# VS1003.net
KiCad netlist of a schematic drawn in Altium Designer
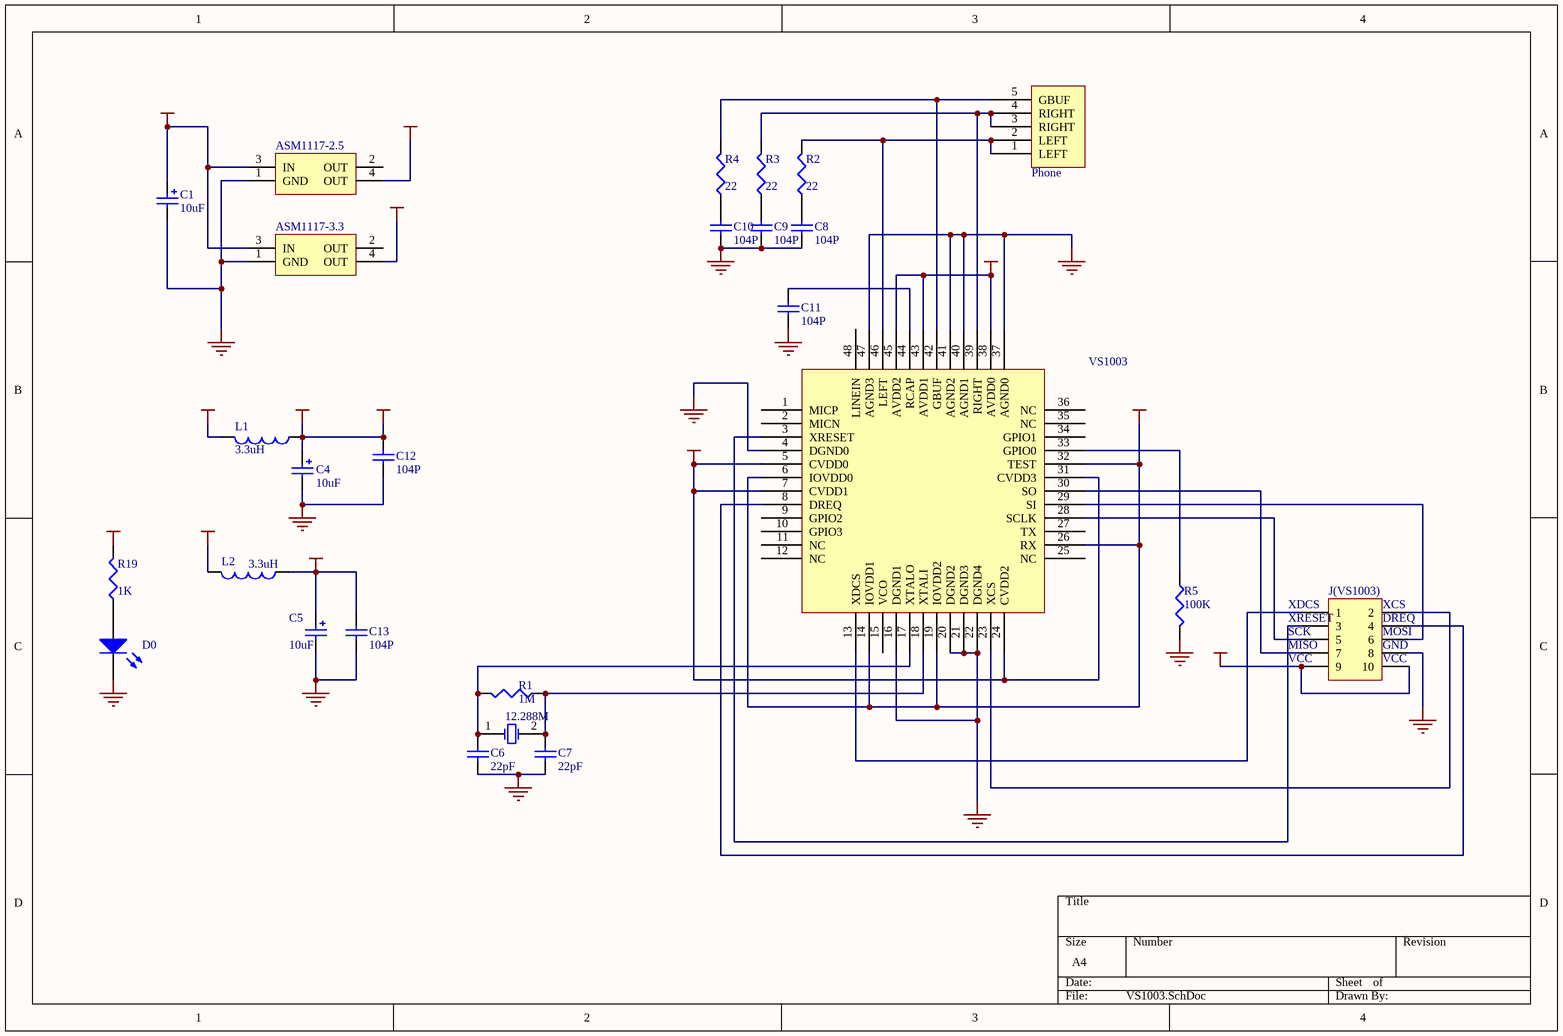
[diagram p0: VS1003.SchDoc]

(export (version "E")
  (design (tool "Eeschema 10.0.6"))
  (components
    (comp (ref "12.288M")
      (value "XTAL")
      (footprint "RAD-0.2")
      (description "Crystal Oscillator")
      (fields (field (name "PUBLISHER") "Altium Limited"))
      (libsource (lib "Miscellaneous Devices") (part "XTAL"))
    )
    (comp (ref "ASM1117-2.5")
      (value "REG1117-5")
      (footprint "ZZ311")
      (description "800mA and 1A Low Dropout Positive Regulator 2.85V, 3.3V, 5V, and Adjustable")
      (fields (field (name "PUBLISHER") "Altium Limited"))
      (libsource (lib "BB Power Mgt Voltage Regulator") (part "REG1117-5"))
    )
    (comp (ref "ASM1117-3.3")
      (value "REG1117-5")
      (footprint "ZZ311")
      (description "800mA and 1A Low Dropout Positive Regulator 2.85V, 3.3V, 5V, and Adjustable")
      (fields (field (name "PUBLISHER") "Altium Limited"))
      (libsource (lib "BB Power Mgt Voltage Regulator") (part "REG1117-5"))
    )
    (comp (ref "C1")
      (value "10uF")
      (footprint "CR3225-1210")
      (description "Polarized Capacitor (Surface Mount)")
      (fields (field (name "Comment") "Cap Pol3") (field (name "PUBLISHER") "Altium Limited"))
      (libsource (lib "Miscellaneous Devices") (part "Cap Pol3"))
    )
    (comp (ref "C4")
      (value "10uF")
      (footprint "CR3225-1210")
      (description "Polarized Capacitor (Surface Mount)")
      (fields (field (name "Comment") "Cap Pol3") (field (name "PUBLISHER") "Altium Limited"))
      (libsource (lib "Miscellaneous Devices") (part "Cap Pol3"))
    )
    (comp (ref "C5")
      (value "10uF")
      (footprint "CR3225-1210")
      (description "Polarized Capacitor (Surface Mount)")
      (fields (field (name "Comment") "Cap Pol3") (field (name "PUBLISHER") "Altium Limited"))
      (libsource (lib "Miscellaneous Devices") (part "Cap Pol3"))
    )
    (comp (ref "C6")
      (value "22pF")
      (footprint "CR2012-0805")
      (description "Capacitor (Semiconductor SIM Model)")
      (fields (field (name "Comment") "Cap Semi") (field (name "PUBLISHER") "Altium Limited"))
      (libsource (lib "Miscellaneous Devices") (part "Cap Semi"))
    )
    (comp (ref "C7")
      (value "22pF")
      (footprint "CR2012-0805")
      (description "Capacitor (Semiconductor SIM Model)")
      (fields (field (name "Comment") "Cap Semi") (field (name "PUBLISHER") "Altium Limited"))
      (libsource (lib "Miscellaneous Devices") (part "Cap Semi"))
    )
    (comp (ref "C8")
      (value "104P")
      (footprint "CR2012-0805")
      (description "Capacitor (Semiconductor SIM Model)")
      (fields (field (name "Comment") "Cap Semi") (field (name "PUBLISHER") "Altium Limited"))
      (libsource (lib "Miscellaneous Devices") (part "Cap Semi"))
    )
    (comp (ref "C9")
      (value "104P")
      (footprint "CR2012-0805")
      (description "Capacitor (Semiconductor SIM Model)")
      (fields (field (name "Comment") "Cap Semi") (field (name "PUBLISHER") "Altium Limited"))
      (libsource (lib "Miscellaneous Devices") (part "Cap Semi"))
    )
    (comp (ref "C10")
      (value "104P")
      (footprint "CR2012-0805")
      (description "Capacitor (Semiconductor SIM Model)")
      (fields (field (name "Comment") "Cap Semi") (field (name "PUBLISHER") "Altium Limited"))
      (libsource (lib "Miscellaneous Devices") (part "Cap Semi"))
    )
    (comp (ref "C11")
      (value "104P")
      (footprint "CR2012-0805")
      (description "Capacitor (Semiconductor SIM Model)")
      (fields (field (name "Comment") "Cap Semi") (field (name "PUBLISHER") "Altium Limited"))
      (libsource (lib "Miscellaneous Devices") (part "Cap Semi"))
    )
    (comp (ref "C12")
      (value "104P")
      (footprint "CR2012-0805")
      (description "Capacitor (Semiconductor SIM Model)")
      (fields (field (name "Comment") "Cap Semi") (field (name "PUBLISHER") "Altium Limited"))
      (libsource (lib "Miscellaneous Devices") (part "Cap Semi"))
    )
    (comp (ref "C13")
      (value "104P")
      (footprint "CR2012-0805")
      (description "Capacitor (Semiconductor SIM Model)")
      (fields (field (name "Comment") "Cap Semi") (field (name "PUBLISHER") "Altium Limited"))
      (libsource (lib "Miscellaneous Devices") (part "Cap Semi"))
    )
    (comp (ref "D0")
      (value "LED2")
      (footprint "R2012-0805")
      (description "Typical RED, GREEN, YELLOW, AMBER GaAs LED")
      (fields (field (name "PUBLISHER") "Altium Limited"))
      (libsource (lib "Miscellaneous Devices") (part "LED2"))
    )
    (comp (ref "J(VS1003)")
      (value "Header 5X2")
      (footprint "HDR2X5")
      (description "Header, 5-Pin, Dual row")
      (fields (field (name "PUBLISHER") "Altium Limited"))
      (libsource (lib "Miscellaneous Connectors") (part "Header 5X2"))
    )
    (comp (ref "L1")
      (value "3.3uH")
      (footprint "R2012-0805")
      (description "Inductor")
      (fields (field (name "PUBLISHER") "Altium Limited"))
      (libsource (lib "Miscellaneous Devices") (part "Inductor"))
    )
    (comp (ref "L2")
      (value "3.3uH")
      (footprint "R2012-0805")
      (description "Inductor")
      (fields (field (name "PUBLISHER") "Altium Limited"))
      (libsource (lib "Miscellaneous Devices") (part "Inductor"))
    )
    (comp (ref "Phone")
      (value "Earphone")
      (footprint "Earphone")
      (libsource (lib "Earphone") (part "Earphone"))
    )
    (comp (ref "R1")
      (value "1M")
      (footprint "R2012-0805")
      (description "Resistor")
      (fields (field (name "Comment") "Res3") (field (name "PUBLISHER") "Altium Limited"))
      (libsource (lib "Miscellaneous Devices") (part "Res3"))
    )
    (comp (ref "R2")
      (value "22")
      (footprint "R2012-0805")
      (description "Resistor")
      (fields (field (name "Comment") "Res3") (field (name "PUBLISHER") "Altium Limited"))
      (libsource (lib "Miscellaneous Devices") (part "Res3"))
    )
    (comp (ref "R3")
      (value "22")
      (footprint "R2012-0805")
      (description "Resistor")
      (fields (field (name "Comment") "Res3") (field (name "PUBLISHER") "Altium Limited"))
      (libsource (lib "Miscellaneous Devices") (part "Res3"))
    )
    (comp (ref "R4")
      (value "22")
      (footprint "R2012-0805")
      (description "Resistor")
      (fields (field (name "Comment") "Res3") (field (name "PUBLISHER") "Altium Limited"))
      (libsource (lib "Miscellaneous Devices") (part "Res3"))
    )
    (comp (ref "R5")
      (value "100K")
      (footprint "R2012-0805")
      (description "Resistor")
      (fields (field (name "Comment") "Res3") (field (name "PUBLISHER") "Altium Limited"))
      (libsource (lib "Miscellaneous Devices") (part "Res3"))
    )
    (comp (ref "R19")
      (value "1K")
      (footprint "R2012-0805")
      (description "Resistor")
      (fields (field (name "Comment") "Res3") (field (name "PUBLISHER") "Altium Limited"))
      (libsource (lib "Miscellaneous Devices") (part "Res3"))
    )
    (comp (ref "VS1003") (value "VS1003B") (footprint "TQFP-48") (libsource (lib "VS1003") (part "VS1003B")))
  )
  (nets
    (net (code "1") (name "2.5v") (class "Default")
      (node (ref "ASM1117-2.5") (pin "4") (pinfunction "OUT_4") (pintype "power_in"))
      (node (ref "L2") (pin "2") (pinfunction "2_2") (pintype "passive"))
    )
    (net (code "2") (name "3.3v") (class "Default")
      (node (ref "ASM1117-3.3") (pin "4") (pinfunction "OUT_4") (pintype "power_in"))
      (node (ref "L1") (pin "2") (pinfunction "2_2") (pintype "passive"))
    )
    (net (code "3") (name "AVDD") (class "Default")
      (node (ref "C12") (pin "2") (pinfunction "2_2") (pintype "passive"))
      (node (ref "C4") (pin "1") (pinfunction "1_1") (pintype "passive"))
      (node (ref "L1") (pin "1") (pinfunction "1_1") (pintype "passive"))
      (node (ref "VS1003") (pin "14") (pinfunction "IOVDD1_14") (pintype "passive"))
      (node (ref "VS1003") (pin "19") (pinfunction "IOVDD2_19") (pintype "passive"))
      (node (ref "VS1003") (pin "26") (pinfunction "RX_26") (pintype "passive"))
      (node (ref "VS1003") (pin "32") (pinfunction "TEST_32") (pintype "passive"))
      (node (ref "VS1003") (pin "38") (pinfunction "AVDD0_38") (pintype "passive"))
      (node (ref "VS1003") (pin "43") (pinfunction "AVDD1_43") (pintype "passive"))
      (node (ref "VS1003") (pin "45") (pinfunction "AVDD2_45") (pintype "passive"))
      (node (ref "VS1003") (pin "6") (pinfunction "IOVDD0_6") (pintype "passive"))
    )
    (net (code "4") (name "CVDD") (class "Default")
      (node (ref "C13") (pin "2") (pinfunction "2_2") (pintype "passive"))
      (node (ref "C5") (pin "1") (pinfunction "1_1") (pintype "passive"))
      (node (ref "L2") (pin "1") (pinfunction "1_1") (pintype "passive"))
      (node (ref "VS1003") (pin "24") (pinfunction "CVDD2_24") (pintype "passive"))
      (node (ref "VS1003") (pin "31") (pinfunction "CVDD3_31") (pintype "passive"))
      (node (ref "VS1003") (pin "5") (pinfunction "CVDD0_5") (pintype "passive"))
      (node (ref "VS1003") (pin "7") (pinfunction "CVDD1_7") (pintype "passive"))
    )
    (net (code "5") (name "GND") (class "Default")
      (node (ref "ASM1117-2.5") (pin "1") (pinfunction "GND_1") (pintype "power_in"))
      (node (ref "ASM1117-3.3") (pin "1") (pinfunction "GND_1") (pintype "power_in"))
      (node (ref "C1") (pin "2") (pinfunction "2_2") (pintype "passive"))
      (node (ref "C10") (pin "1") (pinfunction "1_1") (pintype "passive"))
      (node (ref "C11") (pin "1") (pinfunction "1_1") (pintype "passive"))
      (node (ref "C12") (pin "1") (pinfunction "1_1") (pintype "passive"))
      (node (ref "C13") (pin "1") (pinfunction "1_1") (pintype "passive"))
      (node (ref "C4") (pin "2") (pinfunction "2_2") (pintype "passive"))
      (node (ref "C5") (pin "2") (pinfunction "2_2") (pintype "passive"))
      (node (ref "C6") (pin "1") (pinfunction "1_1") (pintype "passive"))
      (node (ref "C7") (pin "2") (pinfunction "2_2") (pintype "passive"))
      (node (ref "C8") (pin "1") (pinfunction "1_1") (pintype "passive"))
      (node (ref "C9") (pin "1") (pinfunction "1_1") (pintype "passive"))
      (node (ref "D0") (pin "2") (pinfunction "K_2") (pintype "passive"))
      (node (ref "J(VS1003)") (pin "8") (pinfunction "8_8") (pintype "passive"))
      (node (ref "R5") (pin "2") (pinfunction "2_2") (pintype "passive"))
      (node (ref "VS1003") (pin "16") (pinfunction "DGND1_16") (pintype "passive"))
      (node (ref "VS1003") (pin "20") (pinfunction "DGND2_20") (pintype "passive"))
      (node (ref "VS1003") (pin "21") (pinfunction "DGND3_21") (pintype "passive"))
      (node (ref "VS1003") (pin "22") (pinfunction "DGND4_22") (pintype "passive"))
      (node (ref "VS1003") (pin "37") (pinfunction "AGND0_37") (pintype "passive"))
      (node (ref "VS1003") (pin "4") (pinfunction "DGND0_4") (pintype "passive"))
      (node (ref "VS1003") (pin "40") (pinfunction "AGND1_40") (pintype "passive"))
      (node (ref "VS1003") (pin "41") (pinfunction "AGND2_41") (pintype "passive"))
      (node (ref "VS1003") (pin "47") (pinfunction "AGND3_47") (pintype "passive"))
    )
    (net (code "6") (name "Net-(12.288M-OSC1)") (class "Default")
      (node (ref "12.288M") (pin "1") (pinfunction "OSC1_1") (pintype "passive"))
      (node (ref "C6") (pin "2") (pinfunction "2_2") (pintype "passive"))
      (node (ref "R1") (pin "2") (pinfunction "2_2") (pintype "passive"))
      (node (ref "VS1003") (pin "17") (pinfunction "XTALO_17") (pintype "passive"))
    )
    (net (code "7") (name "Net-(12.288M-OSC2)") (class "Default")
      (node (ref "12.288M") (pin "2") (pinfunction "OSC2_2") (pintype "passive"))
      (node (ref "C7") (pin "1") (pinfunction "1_1") (pintype "passive"))
      (node (ref "R1") (pin "1") (pinfunction "1_1") (pintype "passive"))
      (node (ref "VS1003") (pin "18") (pinfunction "XTALI_18") (pintype "passive"))
    )
    (net (code "8") (name "Net-(C8-Pad2)") (class "Default")
      (node (ref "C8") (pin "2") (pinfunction "2_2") (pintype "passive"))
      (node (ref "R2") (pin "1") (pinfunction "1_1") (pintype "passive"))
    )
    (net (code "9") (name "Net-(C9-Pad2)") (class "Default")
      (node (ref "C9") (pin "2") (pinfunction "2_2") (pintype "passive"))
      (node (ref "R3") (pin "1") (pinfunction "1_1") (pintype "passive"))
    )
    (net (code "10") (name "Net-(C10-Pad2)") (class "Default")
      (node (ref "C10") (pin "2") (pinfunction "2_2") (pintype "passive"))
      (node (ref "R4") (pin "1") (pinfunction "1_1") (pintype "passive"))
    )
    (net (code "11") (name "Net-(D0-A)") (class "Default")
      (node (ref "D0") (pin "1") (pinfunction "A_1") (pintype "passive"))
      (node (ref "R19") (pin "1") (pinfunction "1_1") (pintype "passive"))
    )
    (net (code "12") (name "Net-(Phone-GBUF)") (class "Default")
      (node (ref "Phone") (pin "5") (pinfunction "GBUF_5") (pintype "passive"))
      (node (ref "R4") (pin "2") (pinfunction "2_2") (pintype "passive"))
      (node (ref "VS1003") (pin "42") (pinfunction "GBUF_42") (pintype "passive"))
    )
    (net (code "13") (name "Net-(VS1003-DREQ)") (class "Default")
      (node (ref "J(VS1003)") (pin "4") (pinfunction "4_4") (pintype "passive"))
      (node (ref "VS1003") (pin "8") (pinfunction "DREQ_8") (pintype "passive"))
    )
    (net (code "14") (name "Net-(VS1003-GPIO0)") (class "Default")
      (node (ref "R5") (pin "1") (pinfunction "1_1") (pintype "passive"))
      (node (ref "VS1003") (pin "33") (pinfunction "GPIO0_33") (pintype "passive"))
    )
    (net (code "15") (name "Net-(VS1003-LEFT)") (class "Default")
      (node (ref "Phone") (pin "1") (pinfunction "LEFT_1") (pintype "passive"))
      (node (ref "Phone") (pin "2") (pinfunction "LEFT_2") (pintype "passive"))
      (node (ref "R2") (pin "2") (pinfunction "2_2") (pintype "passive"))
      (node (ref "VS1003") (pin "46") (pinfunction "LEFT_46") (pintype "passive"))
    )
    (net (code "16") (name "Net-(VS1003-RCAP)") (class "Default")
      (node (ref "C11") (pin "2") (pinfunction "2_2") (pintype "passive"))
      (node (ref "VS1003") (pin "44") (pinfunction "RCAP_44") (pintype "passive"))
    )
    (net (code "17") (name "Net-(VS1003-RIGHT)") (class "Default")
      (node (ref "Phone") (pin "3") (pinfunction "RIGHT_3") (pintype "passive"))
      (node (ref "Phone") (pin "4") (pinfunction "RIGHT_4") (pintype "passive"))
      (node (ref "R3") (pin "2") (pinfunction "2_2") (pintype "passive"))
      (node (ref "VS1003") (pin "39") (pinfunction "RIGHT_39") (pintype "passive"))
    )
    (net (code "18") (name "Net-(VS1003-SCLK)") (class "Default")
      (node (ref "J(VS1003)") (pin "5") (pinfunction "5_5") (pintype "passive"))
      (node (ref "VS1003") (pin "28") (pinfunction "SCLK_28") (pintype "passive"))
    )
    (net (code "19") (name "Net-(VS1003-SI)") (class "Default")
      (node (ref "J(VS1003)") (pin "6") (pinfunction "6_6") (pintype "passive"))
      (node (ref "VS1003") (pin "29") (pinfunction "SI_29") (pintype "passive"))
    )
    (net (code "20") (name "Net-(VS1003-SO)") (class "Default")
      (node (ref "J(VS1003)") (pin "7") (pinfunction "7_7") (pintype "passive"))
      (node (ref "VS1003") (pin "30") (pinfunction "SO_30") (pintype "passive"))
    )
    (net (code "21") (name "Net-(VS1003-XCS)") (class "Default")
      (node (ref "J(VS1003)") (pin "2") (pinfunction "2_2") (pintype "passive"))
      (node (ref "VS1003") (pin "23") (pinfunction "XCS_23") (pintype "passive"))
    )
    (net (code "22") (name "Net-(VS1003-XDCS)") (class "Default")
      (node (ref "J(VS1003)") (pin "1") (pinfunction "1_1") (pintype "passive"))
      (node (ref "VS1003") (pin "13") (pinfunction "XDCS_13") (pintype "passive"))
    )
    (net (code "23") (name "Net-(VS1003-XRESET)") (class "Default")
      (node (ref "J(VS1003)") (pin "3") (pinfunction "3_3") (pintype "passive"))
      (node (ref "VS1003") (pin "3") (pinfunction "XRESET_3") (pintype "passive"))
    )
    (net (code "24") (name "VCC") (class "Default")
      (node (ref "ASM1117-2.5") (pin "3") (pinfunction "IN_3") (pintype "power_in"))
      (node (ref "ASM1117-3.3") (pin "3") (pinfunction "IN_3") (pintype "power_in"))
      (node (ref "C1") (pin "1") (pinfunction "1_1") (pintype "passive"))
      (node (ref "J(VS1003)") (pin "10") (pinfunction "10_10") (pintype "passive"))
      (node (ref "J(VS1003)") (pin "9") (pinfunction "9_9") (pintype "passive"))
      (node (ref "R19") (pin "2") (pinfunction "2_2") (pintype "passive"))
    )
    (net (code "25") (name "unconnected-(ASM1117-2.5-OUT-Pad2)") (class "Default")
      (node (ref "ASM1117-2.5") (pin "2") (pinfunction "OUT_2") (pintype "power_in"))
    )
    (net (code "26") (name "unconnected-(ASM1117-3.3-OUT-Pad2)") (class "Default")
      (node (ref "ASM1117-3.3") (pin "2") (pinfunction "OUT_2") (pintype "power_in"))
    )
    (net (code "27") (name "unconnected-(VS1003-GPIO1-Pad34)") (class "Default")
      (node (ref "VS1003") (pin "34") (pinfunction "GPIO1_34") (pintype "passive"))
    )
    (net (code "28") (name "unconnected-(VS1003-GPIO2-Pad9)") (class "Default")
      (node (ref "VS1003") (pin "9") (pinfunction "GPIO2_9") (pintype "passive"))
    )
    (net (code "29") (name "unconnected-(VS1003-GPIO3-Pad10)") (class "Default")
      (node (ref "VS1003") (pin "10") (pinfunction "GPIO3_10") (pintype "passive"))
    )
    (net (code "30") (name "unconnected-(VS1003-LINEIN-Pad48)") (class "Default")
      (node (ref "VS1003") (pin "48") (pinfunction "LINEIN_48") (pintype "passive"))
    )
    (net (code "31") (name "unconnected-(VS1003-MICN-Pad2)") (class "Default")
      (node (ref "VS1003") (pin "2") (pinfunction "MICN_2") (pintype "passive"))
    )
    (net (code "32") (name "unconnected-(VS1003-MICP-Pad1)") (class "Default")
      (node (ref "VS1003") (pin "1") (pinfunction "MICP_1") (pintype "passive"))
    )
    (net (code "33") (name "unconnected-(VS1003-NC-Pad11)") (class "Default")
      (node (ref "VS1003") (pin "11") (pinfunction "NC_11") (pintype "passive"))
    )
    (net (code "34") (name "unconnected-(VS1003-NC-Pad12)") (class "Default")
      (node (ref "VS1003") (pin "12") (pinfunction "NC_12") (pintype "passive"))
    )
    (net (code "35") (name "unconnected-(VS1003-NC-Pad25)") (class "Default")
      (node (ref "VS1003") (pin "25") (pinfunction "NC_25") (pintype "passive"))
    )
    (net (code "36") (name "unconnected-(VS1003-NC-Pad35)") (class "Default")
      (node (ref "VS1003") (pin "35") (pinfunction "NC_35") (pintype "passive"))
    )
    (net (code "37") (name "unconnected-(VS1003-NC-Pad36)") (class "Default")
      (node (ref "VS1003") (pin "36") (pinfunction "NC_36") (pintype "passive"))
    )
    (net (code "38") (name "unconnected-(VS1003-TX-Pad27)") (class "Default")
      (node (ref "VS1003") (pin "27") (pinfunction "TX_27") (pintype "passive"))
    )
    (net (code "39") (name "unconnected-(VS1003-VCO-Pad15)") (class "Default")
      (node (ref "VS1003") (pin "15") (pinfunction "VCO_15") (pintype "passive"))
    )
  )
)
